# 01_POWER_SUPPLY.net
KiCad netlist of a schematic drawn in Altium Designer
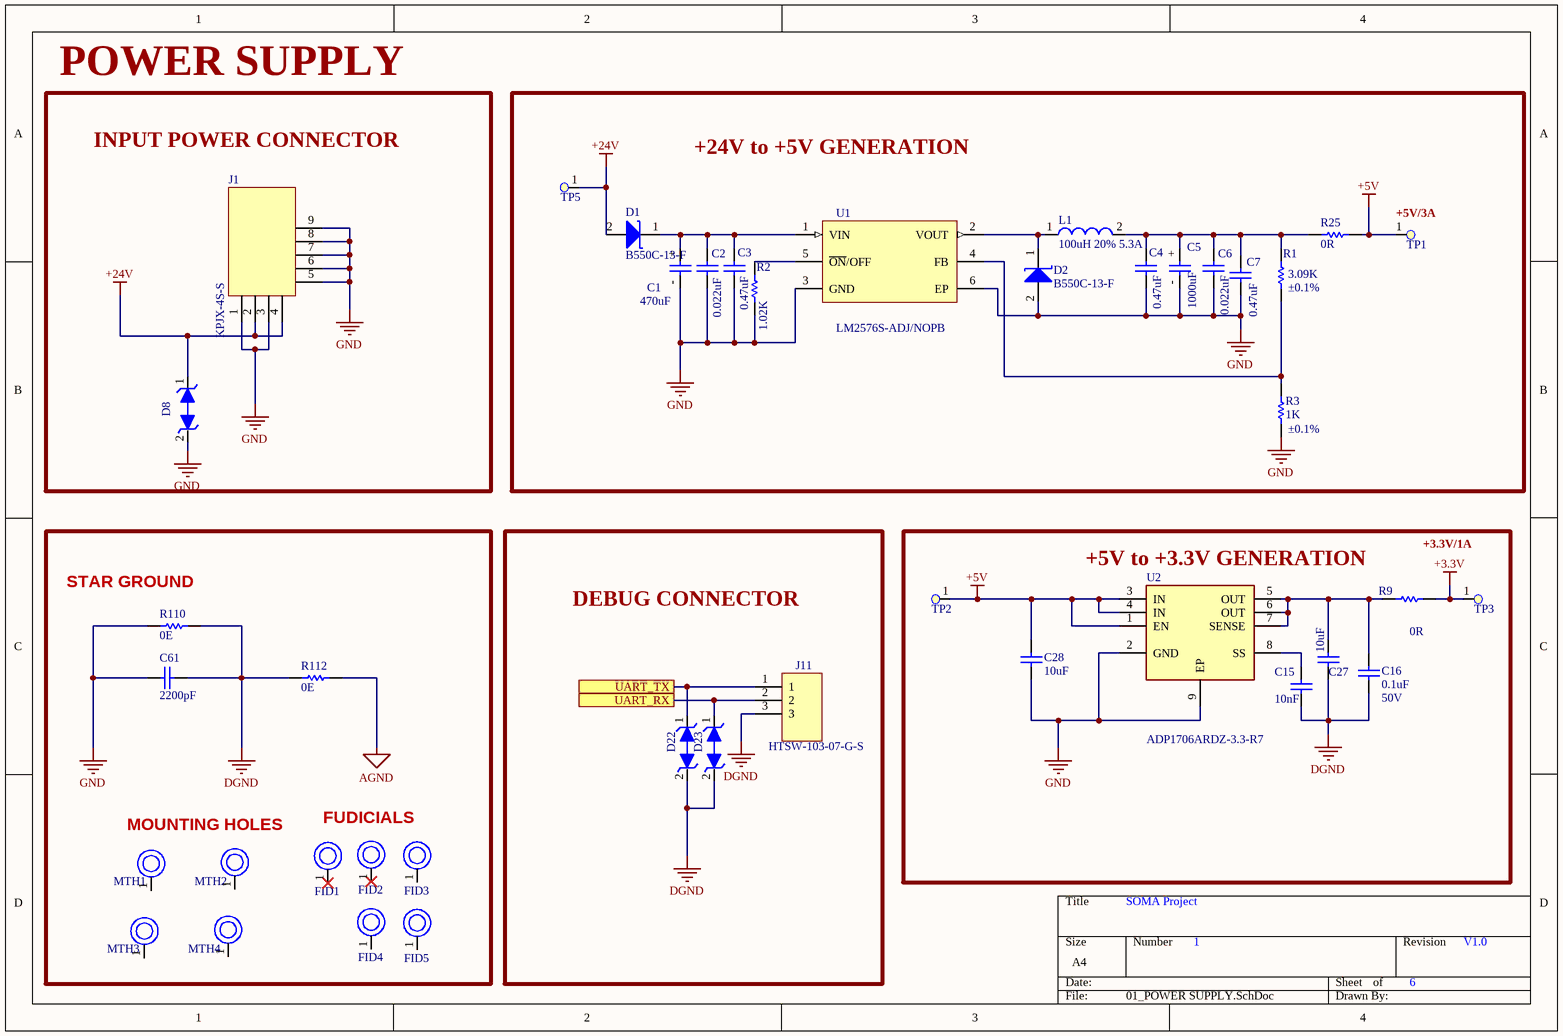
[diagram p0: 01_POWER SUPPLY.SchDoc]

(export (version "E")
  (design (tool "Eeschema 10.0.6"))
  (components
    (comp (ref "C1")
      (value "470uF")
      (footprint "CAPAE1700X1650N")
      (description "CAP ALUM 470UF 20% 63V SMD")
      (fields
        (field (name "MANUFACTURER") "Panasonic Electronic Components")
        (field (name "MANUFACTURER PART NUMBER") "EEV-TG1J471M")
      )
      (libsource (lib "SOMA_15072021") (part "470uF"))
    )
    (comp (ref "C2")
      (value "0.022uF")
      (footprint "C0603")
      (description "CAP CER 0.022UF 100V X7R 0603")
      (fields
        (field (name "MANUFACTURER") "TDK Corporation")
        (field (name "MANUFACTURER PART NUMBER") "C1608X7R2A223K080AA")
      )
      (libsource (lib "SOMA_15072021") (part "CAP CER 0.022UF 100V X7R 0603"))
    )
    (comp (ref "C3")
      (value "0.47uF")
      (footprint "C1206")
      (description "CAP CER 0.47UF 100V X7R 1206")
      (fields
        (field (name "MANUFACTURER") "TDK Corporation")
        (field (name "MANUFACTURER PART NUMBER") "C3216X7R2A474K160AE")
      )
      (libsource (lib "SOMA_15072021") (part "CAP CER 0.47UF 100V X7R 1206"))
    )
    (comp (ref "C4")
      (value "0.47uF")
      (footprint "C1206")
      (description "CAP CER 0.47UF 100V X7R 1206")
      (fields
        (field (name "MANUFACTURER") "TDK Corporation")
        (field (name "MANUFACTURER PART NUMBER") "C3216X7R2A474K160AE")
      )
      (libsource (lib "SOMA_15072021") (part "CAP CER 0.47UF 100V X7R 1206"))
    )
    (comp (ref "C5")
      (value "1000uF")
      (footprint "CAPAE1300X1350N")
      (description "CAP ALUM 1000UF 20% 25V SMD")
      (fields
        (field (name "MANUFACTURER") "United Chemi-Con")
        (field (name "MANUFACTURER PART NUMBER") "EMVA250ARA102MKE0S")
      )
      (libsource (lib "SOMA_15072021") (part "CAP ALUM 1000UF 20% 25V SMD"))
    )
    (comp (ref "C6")
      (value "0.022uF")
      (footprint "C0603")
      (description "CAP CER 0.022UF 100V X7R 0603")
      (fields
        (field (name "MANUFACTURER") "TDK Corporation")
        (field (name "MANUFACTURER PART NUMBER") "C1608X7R2A223K080AA")
      )
      (libsource (lib "SOMA_15072021") (part "CAP CER 0.022UF 100V X7R 0603"))
    )
    (comp (ref "C7")
      (value "0.47uF")
      (footprint "C1206")
      (description "CAP CER 0.47UF 100V X7R 1206")
      (fields
        (field (name "MANUFACTURER") "TDK Corporation")
        (field (name "MANUFACTURER PART NUMBER") "C3216X7R2A474K160AE")
      )
      (libsource (lib "SOMA_15072021") (part "CAP CER 0.47UF 100V X7R 1206"))
    )
    (comp (ref "C15")
      (value "10nF")
      (footprint "C0603")
      (description "CAP CER 0603 10NF 25VDC X8G")
      (fields
        (field (name "MANUFACTURER") "KEMET")
        (field (name "DISTRIBUTOR PART NUMBER") "C0603C103K3TACAUTO")
      )
      (libsource (lib "SOMA_1") (part "CAP CER 0603 10NF 25VDC X8G"))
    )
    (comp (ref "C16")
      (value "0.1uF")
      (footprint "C0402")
      (description "CAP CER 0.1UF 50V X7R 0402")
      (fields
        (field (name "MANUFACTURER") "AVX")
        (field (name "MANUFACTURER PART NUMBER") "04025C104KAT2A")
        (field (name "RATING") "50V")
      )
      (libsource (lib "SOMA_15072021") (part "CAP CER 0.1UF 50V X7R 0402"))
    )
    (comp (ref "C27")
      (value "10uF")
      (footprint "C0603")
      (description "CAP CER 10UF 25V X5R 0603")
      (fields
        (field (name "MANUFACTURER") "Murata Electronics")
        (field (name "DISTRIBUTOR PART NUMBER") "490-10991-1-ND")
      )
      (libsource (lib "SOMA_1") (part "CAP CER 10UF 25V X5R 0603"))
    )
    (comp (ref "C28")
      (value "10uF")
      (footprint "C0603")
      (description "CAP CER 10UF 25V X5R 0603")
      (fields
        (field (name "MANUFACTURER") "Murata Electronics")
        (field (name "DISTRIBUTOR PART NUMBER") "490-10991-1-ND")
      )
      (libsource (lib "SOMA_1") (part "CAP CER 10UF 25V X5R 0603"))
    )
    (comp (ref "C61")
      (value "2200pF")
      (footprint "C1206")
      (description "CAP CER 2200PF 1.5KV X7R 1206")
      (fields
        (field (name "MANUFACTURER") "AVX Corporation")
        (field (name "MANUFACTURER PART NUMBER") "1206SC222KAT2A")
      )
      (libsource (lib "SOMA_15072021") (part "CAP CER 2200PF 1.5KV X7R 1206"))
    )
    (comp (ref "D1")
      (value "DIODE SCHOTTKY 50V 5A SMC")
      (footprint "SOD8060X250N_2A")
      (fields
        (field (name "MANUFACTURER") "Diodes Incorporated")
        (field (name "MANUFACTURER PART NUMBER") "B550C-13-F")
        (field (name "DISTRIBUTOR PART NUMBER") "B550C-FDICT-ND")
      )
      (libsource (lib "SOMA_15072021") (part "B550C-13-F"))
    )
    (comp (ref "D2")
      (value "DIODE SCHOTTKY 50V 5A SMC")
      (footprint "SOD8060X250N_2A")
      (fields
        (field (name "MANUFACTURER") "Diodes Incorporated")
        (field (name "MANUFACTURER PART NUMBER") "B550C-13-F")
        (field (name "DISTRIBUTOR PART NUMBER") "B550C-FDICT-ND")
      )
      (libsource (lib "SOMA_15072021") (part "B550C-13-F"))
    )
    (comp (ref "D8")
      (value "TVS DIODE 24VWM 38.9VC SMC")
      (footprint "SOD8060X260N_BI")
      (description "38.9V Clamp 77.2A Ipp Tvs Diode Surface Mount DO-214AB (SMC)")
      (fields
        (field (name "MANUFACTURER") "Bourns Inc.")
        (field (name "MANUFACTURER PART NUMBER") "SMLJ24CA-Q")
      )
      (libsource (lib "SOMA_1") (part "TVS DIODE 24VWM 38.9VC SMC"))
    )
    (comp (ref "D22")
      (value "TVS DIODE 3.3VWM 11.5VC SOD923")
      (footprint "SOD1006X40N_BI")
      (description "11.5V Clamp 2A (8/20µs) Ipp Tvs Diode Surface Mount SOD-923")
      (fields
        (field (name "MANUFACTURER PART NUMBER") "ESD9B3.3ST5G")
        (field (name "MANUFACTURER") "ON Semiconductor")
      )
      (libsource (lib "SOMA_15072021") (part "TVS DIODE 3.3VWM 11.5VC SOD923"))
    )
    (comp (ref "D23")
      (value "TVS DIODE 3.3VWM 11.5VC SOD923")
      (footprint "SOD1006X40N_BI")
      (description "11.5V Clamp 2A (8/20µs) Ipp Tvs Diode Surface Mount SOD-923")
      (fields
        (field (name "MANUFACTURER PART NUMBER") "ESD9B3.3ST5G")
        (field (name "MANUFACTURER") "ON Semiconductor")
      )
      (libsource (lib "SOMA_15072021") (part "TVS DIODE 3.3VWM 11.5VC SOD923"))
    )
    (comp (ref "FID1")
      (value "M3")
      (footprint "FIDUCIAL_40C")
      (libsource (lib "Daughtercard_Library") (part "Fiducial"))
    )
    (comp (ref "FID2")
      (value "M3")
      (footprint "FIDUCIAL_40C")
      (libsource (lib "Daughtercard_Library") (part "Fiducial"))
    )
    (comp (ref "FID3")
      (value "M3")
      (footprint "FIDUCIAL_40C")
      (libsource (lib "Daughtercard_Library") (part "Fiducial"))
    )
    (comp (ref "FID4")
      (value "M3")
      (footprint "FIDUCIAL_40C")
      (libsource (lib "Daughtercard_Library") (part "Fiducial"))
    )
    (comp (ref "FID5")
      (value "M3")
      (footprint "FIDUCIAL_40C")
      (libsource (lib "Daughtercard_Library") (part "Fiducial"))
    )
    (comp (ref "J1")
      (value "KPJX-4S-S")
      (footprint "KYCON_KPJX-4S -S")
      (description "4 (Power) Position Circular Connector Jack, Female Sockets Solder")
      (fields
        (field (name "MANUFACTURER") "Kycon, Inc.")
        (field (name "DISTRIBUTOR PART NUMBER") "2092-KPJX-4S-S-ND")
      )
      (libsource (lib "SOMA_15072021") (part "CONN JACK FMALE 4POS TIN SOLDER"))
    )
    (comp (ref "J11")
      (value "HTSW-103-07-G-S")
      (footprint "BERG_1X3")
      (description "Connector Header Through Hole 3 position 0.100\" (2.54mm)")
      (fields
        (field (name "DISTRIBUTOR PART NUMBER") "SAM8814-ND")
        (field (name "MANUFACTURER") "Samtec Inc.")
      )
      (libsource (lib "SOMA_15072021") (part "CONN HEADER VERT 3POS 2.54MM"))
    )
    (comp (ref "L1")
      (value "100uH 20% 5.3A")
      (footprint "IND_MGV1707101M-10")
      (description "FIXED IND 100UH 5.3A 118MOHM SMD")
      (fields
        (field (name "MANUFACTURER") "Laird-Signal Integrity Products")
        (field (name "DISTRIBUTOR PART NUMBER") "240-3213-1-ND")
      )
      (libsource (lib "SOMA_15072021") (part "FIXED IND 100UH 5.3A 118MOHM SMD"))
    )
    (comp (ref "MTH1")
      (value "M3")
      (footprint "MH")
      (libsource (lib "Daughtercard_Library") (part "Fiducial"))
    )
    (comp (ref "MTH2")
      (value "M3")
      (footprint "MH")
      (libsource (lib "Daughtercard_Library") (part "Fiducial"))
    )
    (comp (ref "MTH3")
      (value "M3")
      (footprint "MH")
      (libsource (lib "Daughtercard_Library") (part "Fiducial"))
    )
    (comp (ref "MTH4")
      (value "M3")
      (footprint "MH")
      (libsource (lib "Daughtercard_Library") (part "Fiducial"))
    )
    (comp (ref "R1")
      (value "3.09K")
      (footprint "R1206")
      (description "RES SMD 3.09K OHM 0.1% 1/4W 1206")
      (fields
        (field (name "MANUFACTURER") "Panasonic")
        (field (name "DISTRIBUTOR PART NUMBER") "P3.09KBCCT-ND")
        (field (name "TOLERANCE") "±0.1%")
      )
      (libsource (lib "SOMA_15072021") (part "RES SMD 3.09K OHM 0.1% 1/4W 1206"))
    )
    (comp (ref "R2")
      (value "1.02K")
      (footprint "R1206")
      (description "RES SMD 1.02K OHM 1% 1/4W 1206")
      (fields
        (field (name "MANUFACTURER") "Vishay Dale")
        (field (name "DISTRIBUTOR PART NUMBER") "541-1.02KFCT-ND")
      )
      (libsource (lib "SOMA_15072021") (part "RES SMD 1.02K OHM 1% 1/4W 1206"))
    )
    (comp (ref "R3")
      (value "1K")
      (footprint "R0805")
      (description "RES 1K OHM 0.1% 1/8W 0805")
      (fields
        (field (name "TOLERANCE") "±0.1%")
        (field (name "MANUFACTURER") "Panasonic")
        (field (name "DISTRIBUTOR PART NUMBER") "P1.0KDACT-ND")
      )
      (libsource (lib "SOMA_15072021") (part "RES 1K OHM 0.1% 1/8W 0805"))
    )
    (comp (ref "R9")
      (value "0R")
      (footprint "R1206")
      (description "RES 0 OHM JUMPER 1/4W 1206")
      (fields
        (field (name "MANUFACTURER") "Yageo")
        (field (name "DISTRIBUTOR PART NUMBER") "13-RC1206JR-100RLTR-ND")
      )
      (libsource (lib "SOMA_15072021") (part "RES 0 OHM JUMPER 1/4W 1206"))
    )
    (comp (ref "R25")
      (value "0R")
      (footprint "R1206")
      (description "RES 0 OHM JUMPER 1/4W 1206")
      (fields
        (field (name "MANUFACTURER") "Yageo")
        (field (name "DISTRIBUTOR PART NUMBER") "13-RC1206JR-100RLTR-ND")
      )
      (libsource (lib "SOMA_15072021") (part "RES 0 OHM JUMPER 1/4W 1206"))
    )
    (comp (ref "R110")
      (value "0E")
      (footprint "R0603")
      (description "RES SMD 0 OHM JUMPER 1/10W 0603")
      (fields
        (field (name "MANUFACTURER PART NUMBER") "RC0603JR-070RL")
        (field (name "MANUFACTURER") "Yageo")
      )
      (libsource (lib "Daughtercard_Library") (part "RES SMD 0 OHM JUMPER 1/10W 0603"))
    )
    (comp (ref "R112")
      (value "0E")
      (footprint "R0603")
      (description "RES SMD 0 OHM JUMPER 1/10W 0603")
      (fields
        (field (name "MANUFACTURER PART NUMBER") "RC0603JR-070RL")
        (field (name "MANUFACTURER") "Yageo")
      )
      (libsource (lib "Daughtercard_Library") (part "RES SMD 0 OHM JUMPER 1/10W 0603"))
    )
    (comp (ref "TP1")
      (value "Test Point,1.6mm Diameter,SMD")
      (footprint "TP_63C")
      (libsource (lib "SOMA_1") (part "Test Point,1.6mm Diameter,SMD"))
    )
    (comp (ref "TP2")
      (value "Test Point,1.6mm Diameter,SMD")
      (footprint "TP_63C")
      (libsource (lib "SOMA_1") (part "Test Point,1.6mm Diameter,SMD"))
    )
    (comp (ref "TP3")
      (value "Test Point,1.6mm Diameter,SMD")
      (footprint "TP_63C")
      (libsource (lib "SOMA_1") (part "Test Point,1.6mm Diameter,SMD"))
    )
    (comp (ref "TP5")
      (value "Test Point,1.6mm Diameter,SMD")
      (footprint "TP_63C")
      (libsource (lib "SOMA_1") (part "Test Point,1.6mm Diameter,SMD"))
    )
    (comp (ref "U1")
      (value "LM2576S-ADJ/NOPB")
      (footprint "TO-263-6_LM2576S")
      (fields
        (field (name "MANUFACTURER") "Texas Instruments")
        (field (name "DISTRIBUTOR PART NUMBER") "LM2576S-ADJ/NOPB-ND")
        (field (name "TOLERANCE") "NA")
      )
      (libsource (lib "SOMA_15072021") (part "IC REG BUCK ADJ 3A TO263-5"))
    )
    (comp (ref "U2")
      (value "IC REG LINEAR 3.3V 1A 8SOIC")
      (footprint "SOIC127P600X170-9N")
      (description "Linear Voltage Regulator IC Positive Fixed 1 Output 1A 8-SOIC-EP")
      (fields
        (field (name "MANUFACTURER") "Analog Devices Inc.")
        (field (name "DISTRIBUTOR PART NUMBER") "ADP1706ARDZ-3.3-R7CT-ND")
        (field (name "MANUFACTURER PART NUMBER") "ADP1706ARDZ-3.3-R7")
      )
      (libsource (lib "SOMA_15072021") (part "IC REG LINEAR 3.3V 1A 8SOIC"))
    )
  )
  (nets
    (net (code "1") (name "+3.3V") (class "Default")
      (node (ref "R9") (pin "2") (pinfunction "2_2") (pintype "passive"))
      (node (ref "TP3") (pin "1") (pinfunction "0_1") (pintype "passive"))
    )
    (net (code "2") (name "+5V") (class "Default")
      (node (ref "C28") (pin "2") (pinfunction "2_2") (pintype "passive"))
      (node (ref "R25") (pin "2") (pinfunction "2_2") (pintype "passive"))
      (node (ref "TP1") (pin "1") (pinfunction "0_1") (pintype "passive"))
      (node (ref "TP2") (pin "1") (pinfunction "0_1") (pintype "passive"))
      (node (ref "U2") (pin "1") (pinfunction "EN_1") (pintype "passive"))
      (node (ref "U2") (pin "3") (pinfunction "IN_3") (pintype "passive"))
      (node (ref "U2") (pin "4") (pinfunction "IN_4") (pintype "passive"))
    )
    (net (code "3") (name "+24V") (class "Default")
      (node (ref "D1") (pin "2") (pinfunction "A_2") (pintype "passive"))
      (node (ref "D8") (pin "1") (pinfunction "K_1") (pintype "passive"))
      (node (ref "J1") (pin "2") (pinfunction "2_2") (pintype "passive"))
      (node (ref "J1") (pin "4") (pinfunction "4_4") (pintype "passive"))
      (node (ref "TP5") (pin "1") (pinfunction "0_1") (pintype "passive"))
    )
    (net (code "4") (name "/UART_RX") (class "Default")
      (node (ref "D23") (pin "1") (pinfunction "K_1") (pintype "passive"))
      (node (ref "J11") (pin "2") (pinfunction "2_2") (pintype "passive"))
    )
    (net (code "5") (name "/UART_TX") (class "Default")
      (node (ref "D22") (pin "1") (pinfunction "K_1") (pintype "passive"))
      (node (ref "J11") (pin "1") (pinfunction "1_1") (pintype "passive"))
    )
    (net (code "6") (name "AGND") (class "Default")
      (node (ref "R112") (pin "2") (pinfunction "2_2") (pintype "passive"))
    )
    (net (code "7") (name "DGND") (class "Default")
      (node (ref "C15") (pin "1") (pinfunction "1_1") (pintype "passive"))
      (node (ref "C16") (pin "1") (pinfunction "1_1") (pintype "passive"))
      (node (ref "C27") (pin "1") (pinfunction "1_1") (pintype "passive"))
      (node (ref "C61") (pin "2") (pinfunction "2_2") (pintype "passive"))
      (node (ref "D22") (pin "2") (pinfunction "A_2") (pintype "passive"))
      (node (ref "D23") (pin "2") (pinfunction "A_2") (pintype "passive"))
      (node (ref "J11") (pin "3") (pinfunction "3_3") (pintype "passive"))
      (node (ref "R110") (pin "2") (pinfunction "2_2") (pintype "passive"))
      (node (ref "R112") (pin "1") (pinfunction "1_1") (pintype "passive"))
    )
    (net (code "8") (name "GND") (class "Default")
      (node (ref "C1") (pin "-") (pinfunction "2_-") (pintype "passive"))
      (node (ref "C2") (pin "2") (pinfunction "2_2") (pintype "passive"))
      (node (ref "C28") (pin "1") (pinfunction "1_1") (pintype "passive"))
      (node (ref "C3") (pin "1") (pinfunction "1_1") (pintype "passive"))
      (node (ref "C4") (pin "1") (pinfunction "1_1") (pintype "passive"))
      (node (ref "C5") (pin "-") (pinfunction "2_-") (pintype "passive"))
      (node (ref "C6") (pin "1") (pinfunction "1_1") (pintype "passive"))
      (node (ref "C61") (pin "1") (pinfunction "1_1") (pintype "passive"))
      (node (ref "C7") (pin "2") (pinfunction "2_2") (pintype "passive"))
      (node (ref "D2") (pin "2") (pinfunction "A_2") (pintype "passive"))
      (node (ref "D8") (pin "2") (pinfunction "A_2") (pintype "passive"))
      (node (ref "J1") (pin "1") (pinfunction "1_1") (pintype "passive"))
      (node (ref "J1") (pin "3") (pinfunction "3_3") (pintype "passive"))
      (node (ref "J1") (pin "5") (pinfunction "5_5") (pintype "passive"))
      (node (ref "J1") (pin "6") (pinfunction "6_6") (pintype "passive"))
      (node (ref "J1") (pin "7") (pinfunction "7_7") (pintype "passive"))
      (node (ref "J1") (pin "8") (pinfunction "8_8") (pintype "passive"))
      (node (ref "J1") (pin "9") (pinfunction "9_9") (pintype "passive"))
      (node (ref "R110") (pin "1") (pinfunction "1_1") (pintype "passive"))
      (node (ref "R2") (pin "1") (pinfunction "1_1") (pintype "passive"))
      (node (ref "R3") (pin "1") (pinfunction "1_1") (pintype "passive"))
      (node (ref "U1") (pin "3") (pinfunction "GND_3") (pintype "passive"))
      (node (ref "U1") (pin "6") (pinfunction "EP_6") (pintype "passive"))
      (node (ref "U2") (pin "2") (pinfunction "GND_2") (pintype "passive"))
      (node (ref "U2") (pin "9") (pinfunction "EP_9") (pintype "passive"))
    )
    (net (code "9") (name "Net-(C1-1)") (class "Default")
      (node (ref "C1") (pin "+") (pinfunction "1_+") (pintype "passive"))
      (node (ref "C2") (pin "1") (pinfunction "1_1") (pintype "passive"))
      (node (ref "C3") (pin "2") (pinfunction "2_2") (pintype "passive"))
      (node (ref "D1") (pin "1") (pinfunction "K_1") (pintype "passive"))
      (node (ref "U1") (pin "1") (pinfunction "VIN_1") (pintype "input"))
    )
    (net (code "10") (name "Net-(C5-1)") (class "Default")
      (node (ref "C4") (pin "2") (pinfunction "2_2") (pintype "passive"))
      (node (ref "C5") (pin "+") (pinfunction "1_+") (pintype "passive"))
      (node (ref "C6") (pin "2") (pinfunction "2_2") (pintype "passive"))
      (node (ref "C7") (pin "1") (pinfunction "1_1") (pintype "passive"))
      (node (ref "L1") (pin "2") (pinfunction "2_2") (pintype "passive"))
      (node (ref "R1") (pin "2") (pinfunction "2_2") (pintype "passive"))
      (node (ref "R25") (pin "1") (pinfunction "1_1") (pintype "passive"))
    )
    (net (code "11") (name "Net-(D2-K)") (class "Default")
      (node (ref "D2") (pin "1") (pinfunction "K_1") (pintype "passive"))
      (node (ref "L1") (pin "1") (pinfunction "1_1") (pintype "passive"))
      (node (ref "U1") (pin "2") (pinfunction "VOUT_2") (pintype "output"))
    )
    (net (code "12") (name "Net-(U1-FB)") (class "Default")
      (node (ref "R1") (pin "1") (pinfunction "1_1") (pintype "passive"))
      (node (ref "R3") (pin "2") (pinfunction "2_2") (pintype "passive"))
      (node (ref "U1") (pin "4") (pinfunction "FB_4") (pintype "passive"))
    )
    (net (code "13") (name "Net-(U1-~{ON}{slash}OFF)") (class "Default")
      (node (ref "R2") (pin "2") (pinfunction "2_2") (pintype "passive"))
      (node (ref "U1") (pin "5") (pinfunction "~{ON}/OFF_5") (pintype "passive"))
    )
    (net (code "14") (name "Net-(U2-SENSE)") (class "Default")
      (node (ref "C16") (pin "2") (pinfunction "2_2") (pintype "passive"))
      (node (ref "C27") (pin "2") (pinfunction "2_2") (pintype "passive"))
      (node (ref "R9") (pin "1") (pinfunction "1_1") (pintype "passive"))
      (node (ref "U2") (pin "5") (pinfunction "OUT_5") (pintype "passive"))
      (node (ref "U2") (pin "6") (pinfunction "OUT_6") (pintype "passive"))
      (node (ref "U2") (pin "7") (pinfunction "SENSE_7") (pintype "passive"))
    )
    (net (code "15") (name "Net-(U2-SS)") (class "Default")
      (node (ref "C15") (pin "2") (pinfunction "2_2") (pintype "passive"))
      (node (ref "U2") (pin "8") (pinfunction "SS_8") (pintype "passive"))
    )
    (net (code "16") (name "unconnected-(FID1-Pad1)") (class "Default")
      (node (ref "FID1") (pin "1") (pintype "passive+no_connect"))
    )
    (net (code "17") (name "unconnected-(FID2-Pad1)") (class "Default")
      (node (ref "FID2") (pin "1") (pintype "passive+no_connect"))
    )
    (net (code "18") (name "unconnected-(FID3-Pad1)") (class "Default")
      (node (ref "FID3") (pin "1") (pintype "passive"))
    )
    (net (code "19") (name "unconnected-(FID4-Pad1)") (class "Default")
      (node (ref "FID4") (pin "1") (pintype "passive"))
    )
    (net (code "20") (name "unconnected-(FID5-Pad1)") (class "Default")
      (node (ref "FID5") (pin "1") (pintype "passive"))
    )
    (net (code "21") (name "unconnected-(MTH1-Pad1)") (class "Default")
      (node (ref "MTH1") (pin "1") (pintype "passive"))
    )
    (net (code "22") (name "unconnected-(MTH2-Pad1)") (class "Default")
      (node (ref "MTH2") (pin "1") (pintype "passive"))
    )
    (net (code "23") (name "unconnected-(MTH3-Pad1)") (class "Default")
      (node (ref "MTH3") (pin "1") (pintype "passive"))
    )
    (net (code "24") (name "unconnected-(MTH4-Pad1)") (class "Default")
      (node (ref "MTH4") (pin "1") (pintype "passive"))
    )
  )
)
